# source_eagle.net
KiCad netlist of a schematic drawn in EAGLE
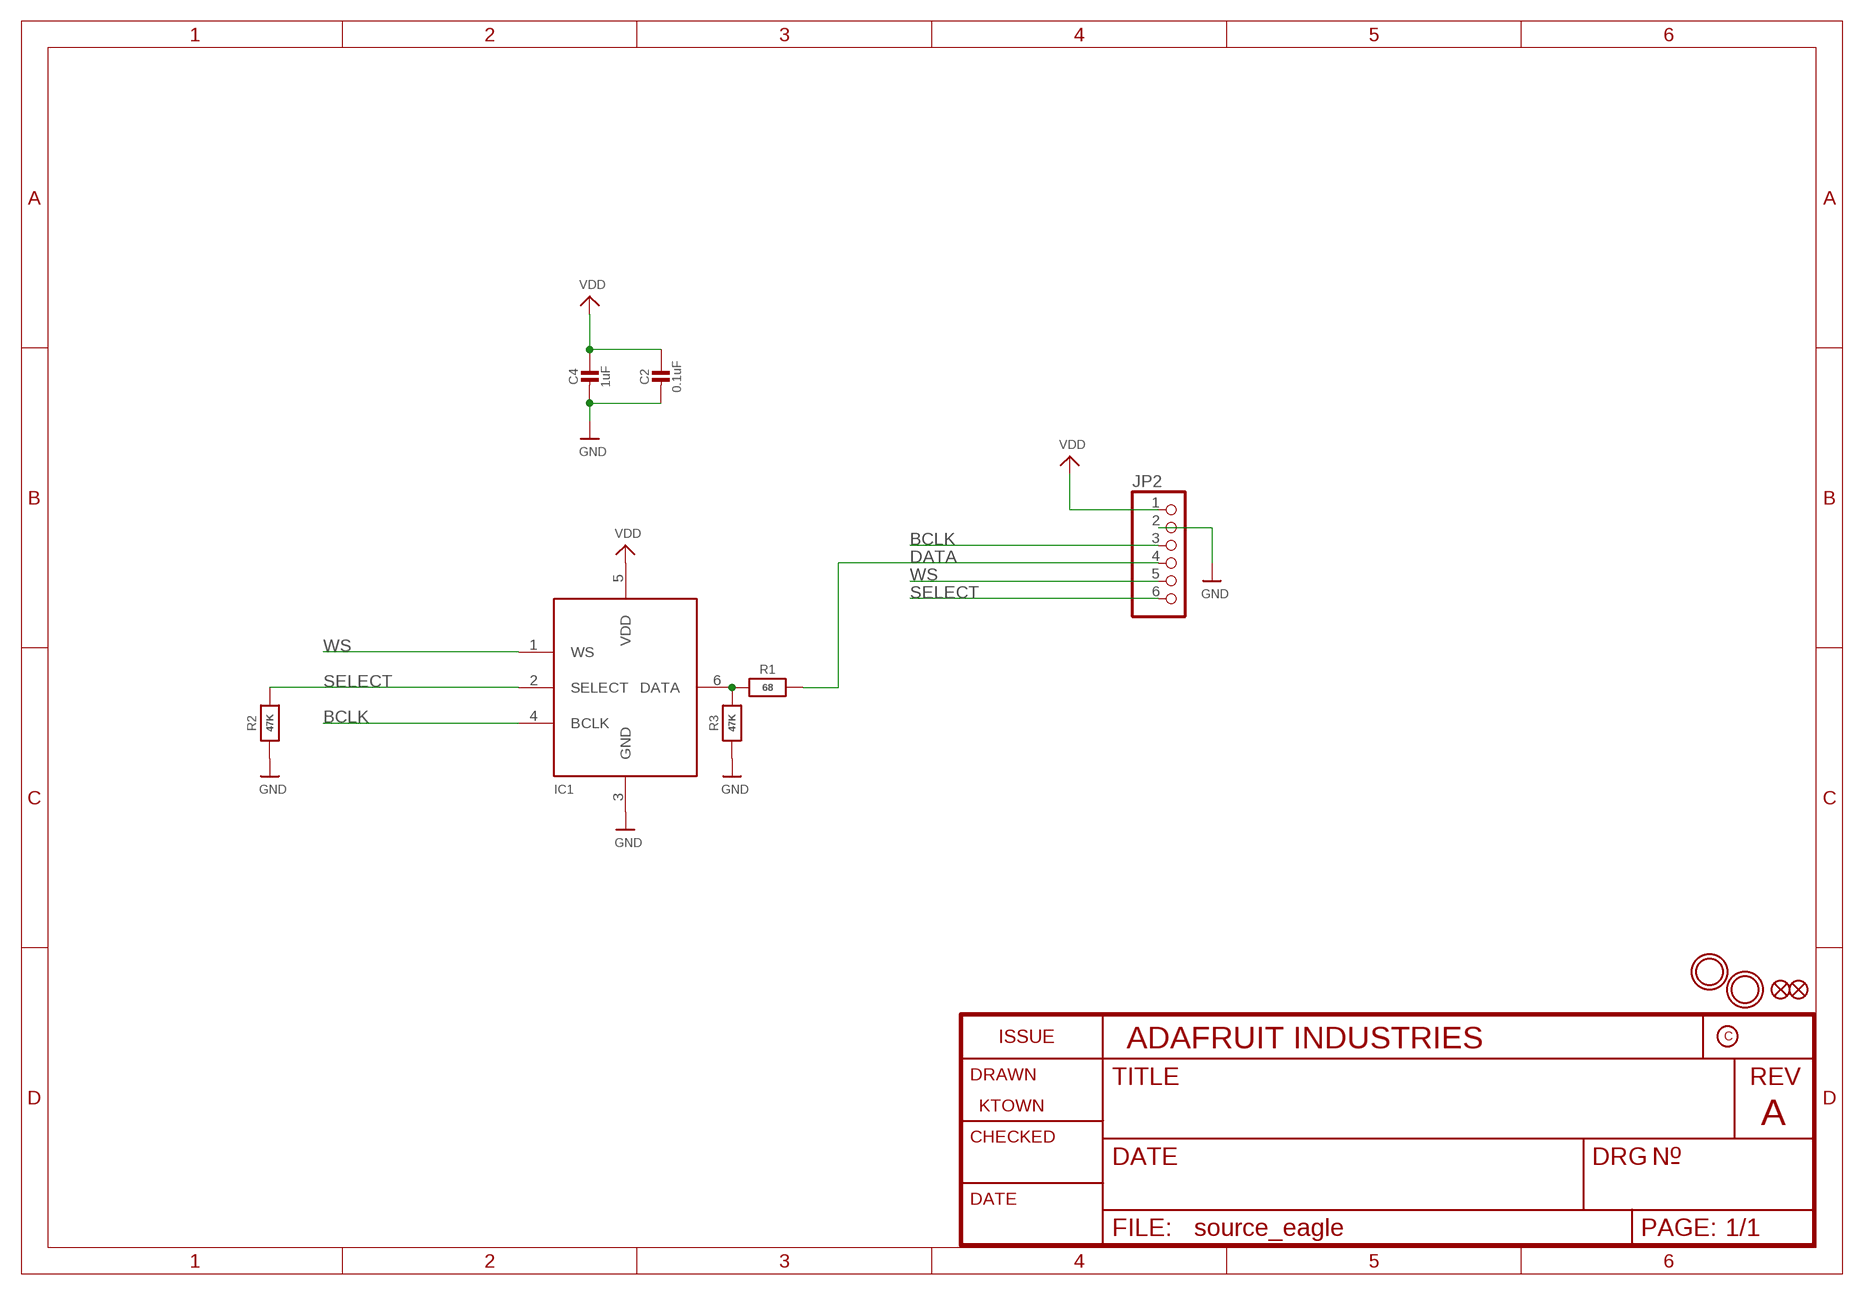
[diagram p0: schematic, sheet 1]

(export (version "E")
  (design (tool "Eeschema 10.0.6"))
  (components
    (comp (ref "C2")
      (value "0.1uF")
      (footprint "eagle-import:0603-NO")
      (libsource (lib "eagle-import") (part "CAP_CERAMIC0603_NO"))
    )
    (comp (ref "C4")
      (value "1uF")
      (footprint "eagle-import:0603-NO")
      (libsource (lib "eagle-import") (part "CAP_CERAMIC0603_NO"))
    )
    (comp (ref "FID1")
      (value "FIDUCIAL_0.5MM")
      (footprint "eagle-import:FIDUCIAL_0.5MM")
      (libsource (lib "eagle-import") (part "FIDUCIAL_0.5MM"))
    )
    (comp (ref "FID2")
      (value "FIDUCIAL_0.5MM")
      (footprint "eagle-import:FIDUCIAL_0.5MM")
      (libsource (lib "eagle-import") (part "FIDUCIAL_0.5MM"))
    )
    (comp (ref "IC1")
      (value "ICS-43434")
      (footprint "eagle-import:SPH0645LM4H")
      (libsource (lib "eagle-import") (part "MIC_I2S_SPH0645"))
    )
    (comp (ref "JP2")
      (value "HEADER-1X6ROUND")
      (footprint "eagle-import:1X06_ROUND")
      (libsource (lib "eagle-import") (part "HEADER-1X6ROUND"))
    )
    (comp (ref "R1")
      (value "68")
      (footprint "eagle-import:0603-NO")
      (libsource (lib "eagle-import") (part "RESISTOR_0603_NOOUT"))
    )
    (comp (ref "R2")
      (value "47K")
      (footprint "eagle-import:0603-NO")
      (libsource (lib "eagle-import") (part "RESISTOR_0603_NOOUT"))
    )
    (comp (ref "R3")
      (value "47K")
      (footprint "eagle-import:0603-NO")
      (libsource (lib "eagle-import") (part "RESISTOR_0603_NOOUT"))
    )
    (comp (ref "U$6")
      (value "MOUNTINGHOLE2.5")
      (footprint "eagle-import:MOUNTINGHOLE_2.5_PLATED")
      (libsource (lib "eagle-import") (part "MOUNTINGHOLE2.5"))
    )
    (comp (ref "U$12")
      (value "MOUNTINGHOLE2.5")
      (footprint "eagle-import:MOUNTINGHOLE_2.5_PLATED")
      (libsource (lib "eagle-import") (part "MOUNTINGHOLE2.5"))
    )
  )
  (nets
    (net (code "1") (name "/BCLK") (class "Default")
      (node (ref "IC1") (pin "4") (pinfunction "BCLK_4") (pintype "input"))
      (node (ref "JP2") (pin "3") (pinfunction "3_3") (pintype "passive"))
    )
    (net (code "2") (name "/DATA") (class "Default")
      (node (ref "JP2") (pin "4") (pinfunction "4_4") (pintype "passive"))
      (node (ref "R1") (pin "2") (pinfunction "2_2") (pintype "passive"))
    )
    (net (code "3") (name "/SELECT") (class "Default")
      (node (ref "IC1") (pin "2") (pinfunction "SELECT_2") (pintype "input"))
      (node (ref "JP2") (pin "6") (pinfunction "6_6") (pintype "passive"))
      (node (ref "R2") (pin "2") (pinfunction "2_2") (pintype "passive"))
    )
    (net (code "4") (name "/WS") (class "Default")
      (node (ref "IC1") (pin "1") (pinfunction "WS_1") (pintype "input"))
      (node (ref "JP2") (pin "5") (pinfunction "5_5") (pintype "passive"))
    )
    (net (code "5") (name "GND") (class "Default")
      (node (ref "C2") (pin "2") (pinfunction "2_2") (pintype "passive"))
      (node (ref "C4") (pin "2") (pinfunction "2_2") (pintype "passive"))
      (node (ref "IC1") (pin "3") (pinfunction "GND_3") (pintype "power_in"))
      (node (ref "JP2") (pin "2") (pinfunction "2_2") (pintype "passive"))
      (node (ref "R2") (pin "1") (pinfunction "1_1") (pintype "passive"))
      (node (ref "R3") (pin "1") (pinfunction "1_1") (pintype "passive"))
    )
    (net (code "6") (name "Net-(IC1-DATA)") (class "Default")
      (node (ref "IC1") (pin "6") (pinfunction "DATA_6") (pintype "output"))
      (node (ref "R1") (pin "1") (pinfunction "1_1") (pintype "passive"))
      (node (ref "R3") (pin "2") (pinfunction "2_2") (pintype "passive"))
    )
    (net (code "7") (name "VDD") (class "Default")
      (node (ref "C2") (pin "1") (pinfunction "1_1") (pintype "passive"))
      (node (ref "C4") (pin "1") (pinfunction "1_1") (pintype "passive"))
      (node (ref "IC1") (pin "5") (pinfunction "VDD_5") (pintype "power_in"))
      (node (ref "JP2") (pin "1") (pinfunction "1_1") (pintype "passive"))
    )
  )
)
